# MultiEffect.net
KiCad netlist of a schematic drawn in EAGLE
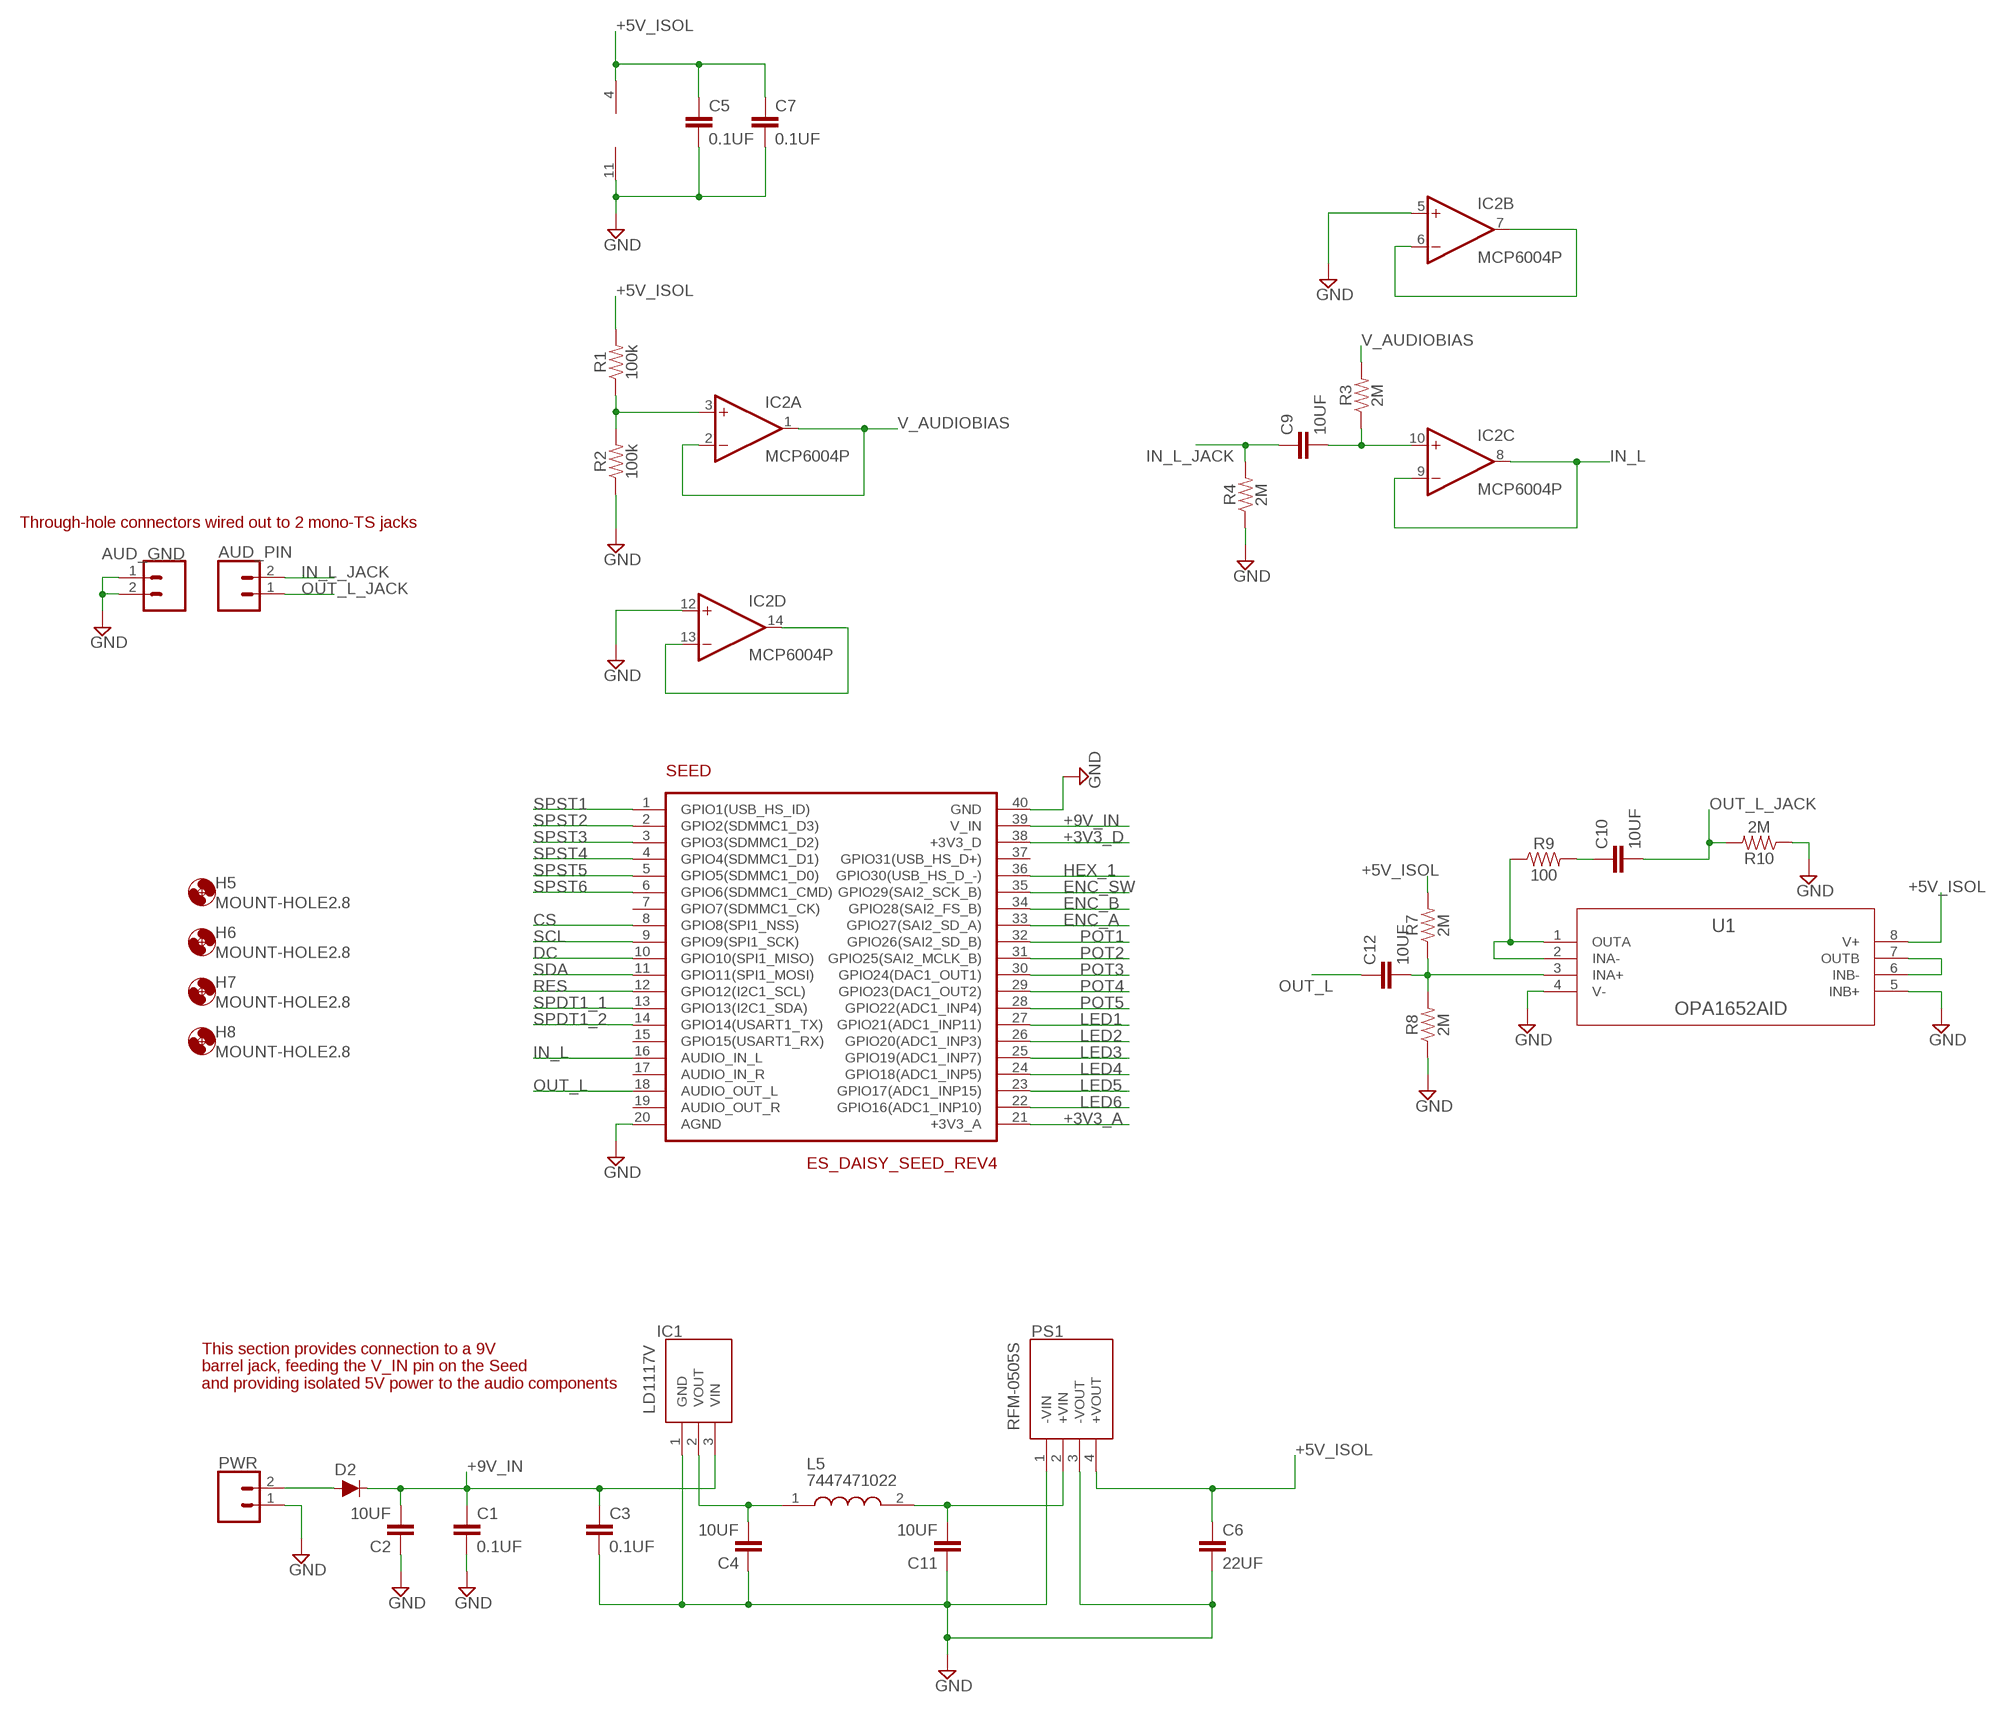
[diagram p0: schematic, sheet 1]
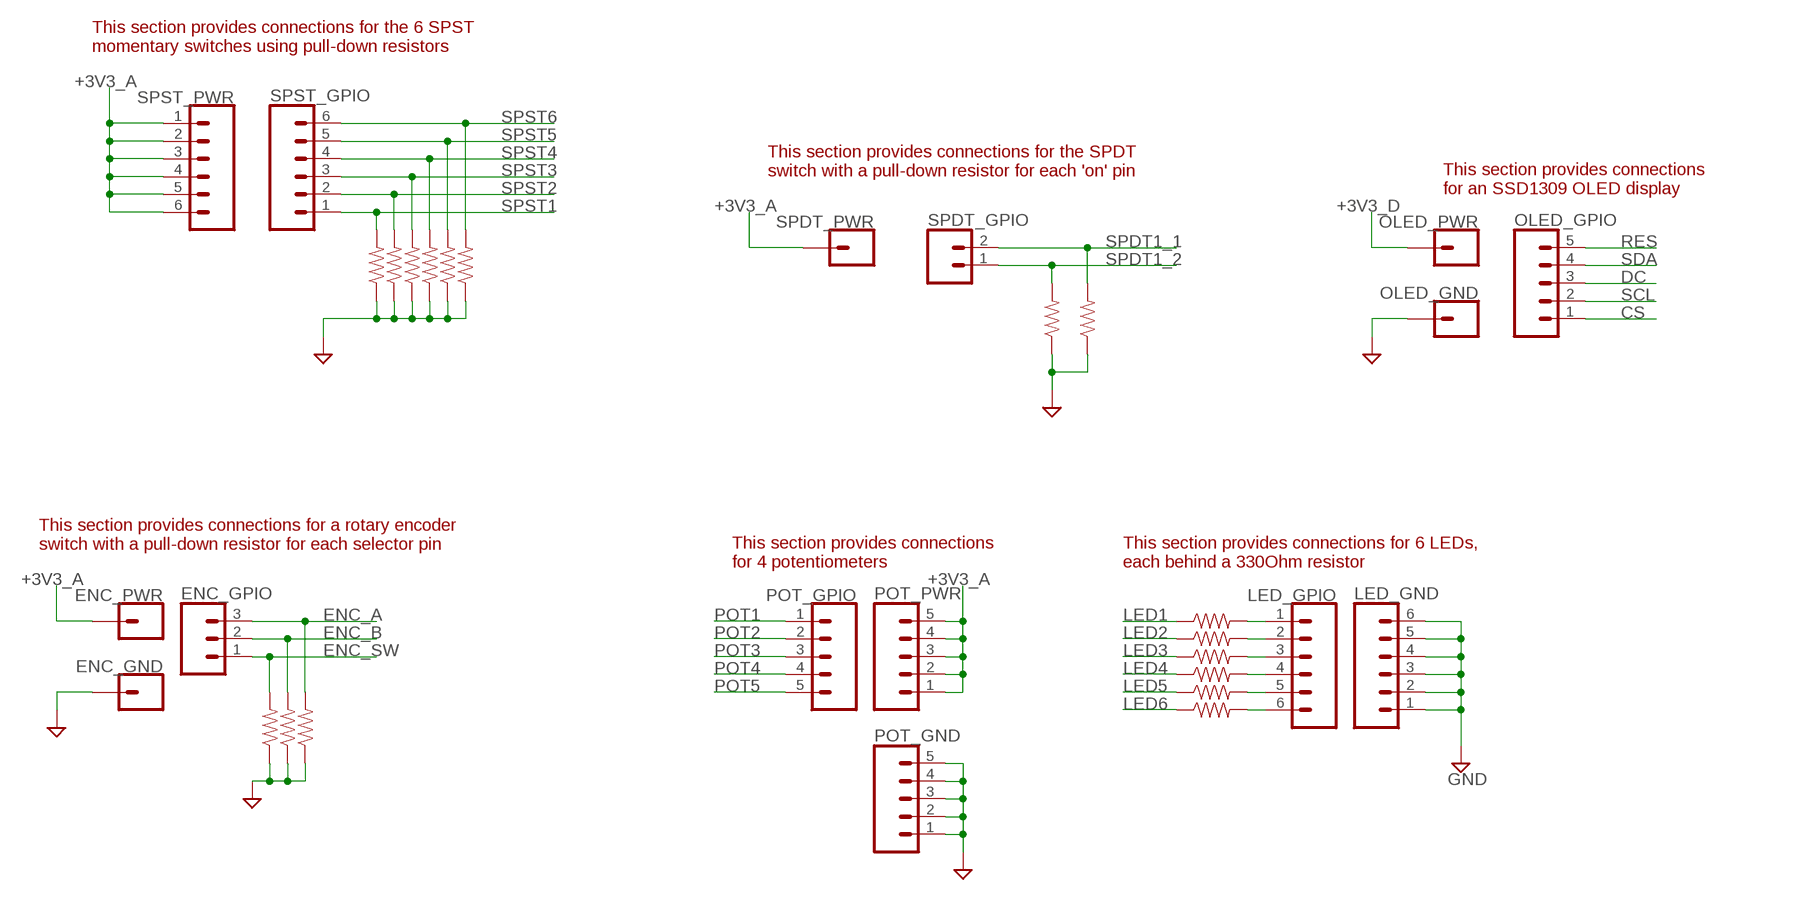
[diagram p1: schematic, sheet 2]

(export (version "E")
  (design (tool "Eeschema 10.0.6"))
  (components
    (comp (ref "AUD_GND")
      (value "CONN_02")
      (footprint "eagle-import:1X02")
      (libsource (lib "eagle-import") (part "CONN_02"))
    )
    (comp (ref "AUD_PIN")
      (value "CONN_02")
      (footprint "eagle-import:1X02")
      (libsource (lib "eagle-import") (part "CONN_02"))
    )
    (comp (ref "C1")
      (value "0.1UF")
      (footprint "eagle-import:CAP-PTH-SMALL-KIT")
      (libsource (lib "eagle-import") (part "0.1UF"))
    )
    (comp (ref "C2")
      (value "10UF")
      (footprint "eagle-import:CAP-PTH-SMALL-KIT")
      (libsource (lib "eagle-import") (part "10UF"))
    )
    (comp (ref "C3")
      (value "0.1UF")
      (footprint "eagle-import:CAP-PTH-SMALL-KIT")
      (libsource (lib "eagle-import") (part "0.1UF"))
    )
    (comp (ref "C4")
      (value "10UF")
      (footprint "eagle-import:CAP-PTH-SMALL-KIT")
      (libsource (lib "eagle-import") (part "10UF"))
    )
    (comp (ref "C5")
      (value "0.1UF")
      (footprint "eagle-import:CAP-PTH-SMALL-KIT")
      (libsource (lib "eagle-import") (part "0.1UF"))
    )
    (comp (ref "C6")
      (value "22UF")
      (footprint "eagle-import:CAP-PTH-SMALL-KIT")
      (libsource (lib "eagle-import") (part "22UF"))
    )
    (comp (ref "C7")
      (value "0.1UF")
      (footprint "eagle-import:CAP-PTH-SMALL-KIT")
      (libsource (lib "eagle-import") (part "0.1UF"))
    )
    (comp (ref "C9")
      (value "10UF")
      (footprint "eagle-import:CAP-PTH-SMALL-KIT")
      (libsource (lib "eagle-import") (part "10UF"))
    )
    (comp (ref "C10")
      (value "10UF")
      (footprint "eagle-import:CAP-PTH-SMALL-KIT")
      (libsource (lib "eagle-import") (part "10UF"))
    )
    (comp (ref "C11")
      (value "10UF")
      (footprint "eagle-import:CAP-PTH-SMALL-KIT")
      (libsource (lib "eagle-import") (part "10UF"))
    )
    (comp (ref "C12")
      (value "10UF")
      (footprint "eagle-import:CAP-PTH-SMALL-KIT")
      (libsource (lib "eagle-import") (part "10UF"))
    )
    (comp (ref "D2")
      (value "200mA/100V/1V")
      (footprint "eagle-import:DIODE-1N4148")
      (libsource (lib "eagle-import") (part "DIODE-1N4148"))
    )
    (comp (ref "H5")
      (value "MOUNT-HOLE2.8")
      (footprint "eagle-import:2,8")
      (libsource (lib "eagle-import") (part "MOUNT-HOLE2.8"))
    )
    (comp (ref "H6")
      (value "MOUNT-HOLE2.8")
      (footprint "eagle-import:2,8")
      (libsource (lib "eagle-import") (part "MOUNT-HOLE2.8"))
    )
    (comp (ref "H7")
      (value "MOUNT-HOLE2.8")
      (footprint "eagle-import:2,8")
      (libsource (lib "eagle-import") (part "MOUNT-HOLE2.8"))
    )
    (comp (ref "H8")
      (value "MOUNT-HOLE2.8")
      (footprint "eagle-import:2,8")
      (libsource (lib "eagle-import") (part "MOUNT-HOLE2.8"))
    )
    (comp (ref "IC1")
      (value "LD1117V")
      (footprint "eagle-import:TO255P460X1020X2008-3P")
      (fields (field (name "MOUSER_PART_NUMBER") "511-LD1117V"))
      (libsource (lib "eagle-import") (part "LD1117V"))
    )
    (comp (ref "IC2")
      (value "MCP6004P")
      (footprint "eagle-import:DIL14")
      (libsource (lib "eagle-import") (part "MCP6004P"))
    )
    (comp (ref "L5")
      (value "7447471022")
      (footprint "eagle-import:WE-TIS_111190")
      (fields (field (name "MOUSER_PART_NUMBER") "710-7447471022"))
      (libsource (lib "eagle-import") (part "7447471022"))
    )
    (comp (ref "PS1")
      (value "RFM-0505S")
      (footprint "eagle-import:RFM0505S")
      (fields (field (name "MOUSER_PART_NUMBER") "919-RFM-0505S"))
      (libsource (lib "eagle-import") (part "RFM-0505S"))
    )
    (comp (ref "PWR")
      (value "CONN_02")
      (footprint "eagle-import:1X02")
      (libsource (lib "eagle-import") (part "CONN_02"))
    )
    (comp (ref "R1")
      (value "100k")
      (footprint "eagle-import:AXIAL-0.3")
      (libsource (lib "eagle-import") (part "100KOHM-HORIZ-1/4W-5%"))
    )
    (comp (ref "R2")
      (value "100k")
      (footprint "eagle-import:AXIAL-0.3")
      (libsource (lib "eagle-import") (part "100KOHM-HORIZ-1/4W-5%"))
    )
    (comp (ref "R3")
      (value "2M")
      (footprint "eagle-import:AXIAL-0.3")
      (libsource (lib "eagle-import") (part "2MOHM-HORIZ-1/4W-5%"))
    )
    (comp (ref "R4")
      (value "2M")
      (footprint "eagle-import:AXIAL-0.3")
      (libsource (lib "eagle-import") (part "2MOHM-HORIZ-1/4W-5%"))
    )
    (comp (ref "R7")
      (value "2M")
      (footprint "eagle-import:AXIAL-0.3")
      (libsource (lib "eagle-import") (part "2MOHM-HORIZ-1/4W-5%"))
    )
    (comp (ref "R8")
      (value "2M")
      (footprint "eagle-import:AXIAL-0.3")
      (libsource (lib "eagle-import") (part "2MOHM-HORIZ-1/4W-5%"))
    )
    (comp (ref "R9")
      (value "100")
      (footprint "eagle-import:AXIAL-0.3")
      (libsource (lib "eagle-import") (part "100OHM-HORIZ-1/4W-1%"))
    )
    (comp (ref "R10")
      (value "2M")
      (footprint "eagle-import:AXIAL-0.3")
      (libsource (lib "eagle-import") (part "2MOHM-HORIZ-1/4W-5%"))
    )
    (comp (ref "SEED")
      (value "ES_DAISY_SEED_REV4")
      (footprint "eagle-import:ES_DAISY_SEED")
      (libsource (lib "eagle-import") (part "ES_DAISY_SEED_REV4"))
    )
    (comp (ref "U1")
      (value "OPA1652AID")
      (footprint "eagle-import:D8")
      (fields
        (field (name "GENERIC_PART_NUMBER") "OPA1652")
        (field (name "MANUFACTURER") "Texas Instruments")
      )
      (libsource (lib "eagle-import") (part "OPA1652AID"))
    )
    (comp (ref "D11")
      (value "10k")
      (footprint "eagle-import:AXIAL-0.3")
      (libsource (lib "eagle-import") (part "10KOHM-HORIZ-1/4W-5%"))
    )
    (comp (ref "D12")
      (value "10k")
      (footprint "eagle-import:AXIAL-0.3")
      (libsource (lib "eagle-import") (part "10KOHM-HORIZ-1/4W-5%"))
    )
    (comp (ref "ENC_GND")
      (value "CONN_01")
      (footprint "eagle-import:1X01")
      (libsource (lib "eagle-import") (part "CONN_01"))
    )
    (comp (ref "ENC_GPIO")
      (value "CONN_03")
      (footprint "eagle-import:1X03")
      (libsource (lib "eagle-import") (part "CONN_03"))
    )
    (comp (ref "ENC_PWR")
      (value "CONN_01")
      (footprint "eagle-import:1X01")
      (libsource (lib "eagle-import") (part "CONN_01"))
    )
    (comp (ref "H2")
      (value "10k")
      (footprint "eagle-import:AXIAL-0.3")
      (libsource (lib "eagle-import") (part "10KOHM-HORIZ-1/4W-5%"))
    )
    (comp (ref "H3")
      (value "10k")
      (footprint "eagle-import:AXIAL-0.3")
      (libsource (lib "eagle-import") (part "10KOHM-HORIZ-1/4W-5%"))
    )
    (comp (ref "H4")
      (value "10k")
      (footprint "eagle-import:AXIAL-0.3")
      (libsource (lib "eagle-import") (part "10KOHM-HORIZ-1/4W-5%"))
    )
    (comp (ref "L1")
      (value "330")
      (footprint "eagle-import:AXIAL-0.3")
      (libsource (lib "eagle-import") (part "330OHM-HORIZ-1/10W-5%"))
    )
    (comp (ref "L2")
      (value "330")
      (footprint "eagle-import:AXIAL-0.3")
      (libsource (lib "eagle-import") (part "330OHM-HORIZ-1/10W-5%"))
    )
    (comp (ref "L3")
      (value "330")
      (footprint "eagle-import:AXIAL-0.3")
      (libsource (lib "eagle-import") (part "330OHM-HORIZ-1/10W-5%"))
    )
    (comp (ref "L4")
      (value "330")
      (footprint "eagle-import:AXIAL-0.3")
      (libsource (lib "eagle-import") (part "330OHM-HORIZ-1/10W-5%"))
    )
    (comp (ref "L6")
      (value "330")
      (footprint "eagle-import:AXIAL-0.3")
      (libsource (lib "eagle-import") (part "330OHM-HORIZ-1/10W-5%"))
    )
    (comp (ref "L7")
      (value "330")
      (footprint "eagle-import:AXIAL-0.3")
      (libsource (lib "eagle-import") (part "330OHM-HORIZ-1/10W-5%"))
    )
    (comp (ref "LED_GND")
      (value "CONN_06SILK_FEMALE_PTH")
      (footprint "eagle-import:1X06")
      (libsource (lib "eagle-import") (part "CONN_06SILK_FEMALE_PTH"))
    )
    (comp (ref "LED_GPIO")
      (value "CONN_06SILK_FEMALE_PTH")
      (footprint "eagle-import:1X06")
      (libsource (lib "eagle-import") (part "CONN_06SILK_FEMALE_PTH"))
    )
    (comp (ref "OLED_GND")
      (value "CONN_01")
      (footprint "eagle-import:1X01")
      (libsource (lib "eagle-import") (part "CONN_01"))
    )
    (comp (ref "OLED_GPIO")
      (value "CONN_05")
      (footprint "eagle-import:1X05")
      (libsource (lib "eagle-import") (part "CONN_05"))
    )
    (comp (ref "OLED_PWR")
      (value "CONN_01")
      (footprint "eagle-import:1X01")
      (libsource (lib "eagle-import") (part "CONN_01"))
    )
    (comp (ref "POT_GND")
      (value "CONN_05")
      (footprint "eagle-import:1X05")
      (libsource (lib "eagle-import") (part "CONN_05"))
    )
    (comp (ref "POT_GPIO")
      (value "CONN_05")
      (footprint "eagle-import:1X05")
      (libsource (lib "eagle-import") (part "CONN_05"))
    )
    (comp (ref "POT_PWR")
      (value "CONN_05")
      (footprint "eagle-import:1X05")
      (libsource (lib "eagle-import") (part "CONN_05"))
    )
    (comp (ref "S1")
      (value "10k")
      (footprint "eagle-import:AXIAL-0.3")
      (libsource (lib "eagle-import") (part "10KOHM-HORIZ-1/4W-5%"))
    )
    (comp (ref "S2")
      (value "10k")
      (footprint "eagle-import:AXIAL-0.3")
      (libsource (lib "eagle-import") (part "10KOHM-HORIZ-1/4W-5%"))
    )
    (comp (ref "S3")
      (value "10k")
      (footprint "eagle-import:AXIAL-0.3")
      (libsource (lib "eagle-import") (part "10KOHM-HORIZ-1/4W-5%"))
    )
    (comp (ref "S4")
      (value "10k")
      (footprint "eagle-import:AXIAL-0.3")
      (libsource (lib "eagle-import") (part "10KOHM-HORIZ-1/4W-5%"))
    )
    (comp (ref "S5")
      (value "10k")
      (footprint "eagle-import:AXIAL-0.3")
      (libsource (lib "eagle-import") (part "10KOHM-HORIZ-1/4W-5%"))
    )
    (comp (ref "S6")
      (value "10k")
      (footprint "eagle-import:AXIAL-0.3")
      (libsource (lib "eagle-import") (part "10KOHM-HORIZ-1/4W-5%"))
    )
    (comp (ref "SPDT_GPIO")
      (value "CONN_02")
      (footprint "eagle-import:1X02")
      (libsource (lib "eagle-import") (part "CONN_02"))
    )
    (comp (ref "SPDT_PWR")
      (value "CONN_01")
      (footprint "eagle-import:1X01")
      (libsource (lib "eagle-import") (part "CONN_01"))
    )
    (comp (ref "SPST_GPIO")
      (value "CONN_06SILK_FEMALE_PTH")
      (footprint "eagle-import:1X06")
      (libsource (lib "eagle-import") (part "CONN_06SILK_FEMALE_PTH"))
    )
    (comp (ref "SPST_PWR")
      (value "CONN_06SILK_FEMALE_PTH")
      (footprint "eagle-import:1X06")
      (libsource (lib "eagle-import") (part "CONN_06SILK_FEMALE_PTH"))
    )
  )
  (nets
    (net (code "1") (name "+3V3_A") (class "Default")
      (node (ref "ENC_PWR") (pin "1") (pinfunction "1_1") (pintype "passive"))
      (node (ref "POT_PWR") (pin "1") (pinfunction "1_1") (pintype "passive"))
      (node (ref "POT_PWR") (pin "2") (pinfunction "2_2") (pintype "passive"))
      (node (ref "POT_PWR") (pin "3") (pinfunction "3_3") (pintype "passive"))
      (node (ref "POT_PWR") (pin "4") (pinfunction "4_4") (pintype "passive"))
      (node (ref "POT_PWR") (pin "5") (pinfunction "5_5") (pintype "passive"))
      (node (ref "SEED") (pin "21") (pinfunction "+3V3_A_21") (pintype "bidirectional"))
      (node (ref "SPDT_PWR") (pin "1") (pinfunction "1_1") (pintype "passive"))
      (node (ref "SPST_PWR") (pin "1") (pinfunction "1_1") (pintype "passive"))
      (node (ref "SPST_PWR") (pin "2") (pinfunction "2_2") (pintype "passive"))
      (node (ref "SPST_PWR") (pin "3") (pinfunction "3_3") (pintype "passive"))
      (node (ref "SPST_PWR") (pin "4") (pinfunction "4_4") (pintype "passive"))
      (node (ref "SPST_PWR") (pin "5") (pinfunction "5_5") (pintype "passive"))
      (node (ref "SPST_PWR") (pin "6") (pinfunction "6_6") (pintype "passive"))
    )
    (net (code "2") (name "+3V3_D") (class "Default")
      (node (ref "OLED_PWR") (pin "1") (pinfunction "1_1") (pintype "passive"))
      (node (ref "SEED") (pin "38") (pinfunction "+3V3_D_38") (pintype "bidirectional"))
    )
    (net (code "3") (name "+5V_ISOL") (class "Default")
      (node (ref "C5") (pin "1") (pinfunction "1_1") (pintype "passive"))
      (node (ref "C6") (pin "1") (pinfunction "1_1") (pintype "passive"))
      (node (ref "C7") (pin "1") (pinfunction "1_1") (pintype "passive"))
      (node (ref "IC2") (pin "4") (pinfunction "V+_4") (pintype "power_in"))
      (node (ref "PS1") (pin "4") (pinfunction "+VOUT_4") (pintype "bidirectional"))
      (node (ref "R1") (pin "P$2") (pinfunction "2_P$2") (pintype "passive"))
      (node (ref "R7") (pin "P$2") (pinfunction "2_P$2") (pintype "passive"))
      (node (ref "U1") (pin "8") (pinfunction "V+_8") (pintype "power_in"))
    )
    (net (code "4") (name "+9V_IN") (class "Default")
      (node (ref "C1") (pin "1") (pinfunction "1_1") (pintype "passive"))
      (node (ref "C2") (pin "2") (pinfunction "2_2") (pintype "passive"))
      (node (ref "C3") (pin "1") (pinfunction "1_1") (pintype "passive"))
      (node (ref "D2") (pin "C") (pinfunction "C_C") (pintype "passive"))
      (node (ref "IC1") (pin "3") (pinfunction "VIN_3") (pintype "bidirectional"))
      (node (ref "SEED") (pin "39") (pinfunction "V_IN_39") (pintype "bidirectional"))
    )
    (net (code "5") (name "CS") (class "Default")
      (node (ref "OLED_GPIO") (pin "1") (pinfunction "1_1") (pintype "passive"))
      (node (ref "SEED") (pin "8") (pinfunction "GPIO8(SPI1_NSS)_8") (pintype "bidirectional"))
    )
    (net (code "6") (name "DC") (class "Default")
      (node (ref "OLED_GPIO") (pin "3") (pinfunction "3_3") (pintype "passive"))
      (node (ref "SEED") (pin "10") (pinfunction "GPIO10(SPI1_MISO)_10") (pintype "bidirectional"))
    )
    (net (code "7") (name "ENC_A") (class "Default")
      (node (ref "ENC_GPIO") (pin "3") (pinfunction "3_3") (pintype "passive"))
      (node (ref "H4") (pin "P$2") (pinfunction "2_P$2") (pintype "passive"))
      (node (ref "SEED") (pin "33") (pinfunction "GPIO27(SAI2_SD_A)_33") (pintype "bidirectional"))
    )
    (net (code "8") (name "ENC_B") (class "Default")
      (node (ref "ENC_GPIO") (pin "2") (pinfunction "2_2") (pintype "passive"))
      (node (ref "H3") (pin "P$2") (pinfunction "2_P$2") (pintype "passive"))
      (node (ref "SEED") (pin "34") (pinfunction "GPIO28(SAI2_FS_B)_34") (pintype "bidirectional"))
    )
    (net (code "9") (name "ENC_SW") (class "Default")
      (node (ref "ENC_GPIO") (pin "1") (pinfunction "1_1") (pintype "passive"))
      (node (ref "H2") (pin "P$2") (pinfunction "2_P$2") (pintype "passive"))
      (node (ref "SEED") (pin "35") (pinfunction "GPIO29(SAI2_SCK_B)_35") (pintype "bidirectional"))
    )
    (net (code "10") (name "GND") (class "Default")
      (node (ref "AUD_GND") (pin "1") (pinfunction "1_1") (pintype "passive"))
      (node (ref "AUD_GND") (pin "2") (pinfunction "2_2") (pintype "passive"))
      (node (ref "C1") (pin "2") (pinfunction "2_2") (pintype "passive"))
      (node (ref "C11") (pin "1") (pinfunction "1_1") (pintype "passive"))
      (node (ref "C2") (pin "1") (pinfunction "1_1") (pintype "passive"))
      (node (ref "C3") (pin "2") (pinfunction "2_2") (pintype "passive"))
      (node (ref "C4") (pin "1") (pinfunction "1_1") (pintype "passive"))
      (node (ref "C5") (pin "2") (pinfunction "2_2") (pintype "passive"))
      (node (ref "C6") (pin "2") (pinfunction "2_2") (pintype "passive"))
      (node (ref "C7") (pin "2") (pinfunction "2_2") (pintype "passive"))
      (node (ref "D11") (pin "P$1") (pinfunction "1_P$1") (pintype "passive"))
      (node (ref "D12") (pin "P$1") (pinfunction "1_P$1") (pintype "passive"))
      (node (ref "ENC_GND") (pin "1") (pinfunction "1_1") (pintype "passive"))
      (node (ref "H2") (pin "P$1") (pinfunction "1_P$1") (pintype "passive"))
      (node (ref "H3") (pin "P$1") (pinfunction "1_P$1") (pintype "passive"))
      (node (ref "H4") (pin "P$1") (pinfunction "1_P$1") (pintype "passive"))
      (node (ref "IC1") (pin "1") (pinfunction "GND_1") (pintype "bidirectional"))
      (node (ref "IC2") (pin "11") (pinfunction "V-_11") (pintype "power_in"))
      (node (ref "IC2") (pin "12") (pinfunction "+IN_12") (pintype "input"))
      (node (ref "IC2") (pin "5") (pinfunction "+IN_5") (pintype "input"))
      (node (ref "LED_GND") (pin "1") (pinfunction "1_1") (pintype "passive"))
      (node (ref "LED_GND") (pin "2") (pinfunction "2_2") (pintype "passive"))
      (node (ref "LED_GND") (pin "3") (pinfunction "3_3") (pintype "passive"))
      (node (ref "LED_GND") (pin "4") (pinfunction "4_4") (pintype "passive"))
      (node (ref "LED_GND") (pin "5") (pinfunction "5_5") (pintype "passive"))
      (node (ref "LED_GND") (pin "6") (pinfunction "6_6") (pintype "passive"))
      (node (ref "OLED_GND") (pin "1") (pinfunction "1_1") (pintype "passive"))
      (node (ref "POT_GND") (pin "1") (pinfunction "1_1") (pintype "passive"))
      (node (ref "POT_GND") (pin "2") (pinfunction "2_2") (pintype "passive"))
      (node (ref "POT_GND") (pin "3") (pinfunction "3_3") (pintype "passive"))
      (node (ref "POT_GND") (pin "4") (pinfunction "4_4") (pintype "passive"))
      (node (ref "POT_GND") (pin "5") (pinfunction "5_5") (pintype "passive"))
      (node (ref "PS1") (pin "1") (pinfunction "-VIN_1") (pintype "bidirectional"))
      (node (ref "PS1") (pin "3") (pinfunction "-VOUT_3") (pintype "bidirectional"))
      (node (ref "PWR") (pin "1") (pinfunction "1_1") (pintype "passive"))
      (node (ref "R10") (pin "P$1") (pinfunction "1_P$1") (pintype "passive"))
      (node (ref "R2") (pin "P$1") (pinfunction "1_P$1") (pintype "passive"))
      (node (ref "R4") (pin "P$1") (pinfunction "1_P$1") (pintype "passive"))
      (node (ref "R8") (pin "P$1") (pinfunction "1_P$1") (pintype "passive"))
      (node (ref "S1") (pin "P$1") (pinfunction "1_P$1") (pintype "passive"))
      (node (ref "S2") (pin "P$1") (pinfunction "1_P$1") (pintype "passive"))
      (node (ref "S3") (pin "P$1") (pinfunction "1_P$1") (pintype "passive"))
      (node (ref "S4") (pin "P$1") (pinfunction "1_P$1") (pintype "passive"))
      (node (ref "S5") (pin "P$1") (pinfunction "1_P$1") (pintype "passive"))
      (node (ref "S6") (pin "P$1") (pinfunction "1_P$1") (pintype "passive"))
      (node (ref "SEED") (pin "20") (pinfunction "AGND_20") (pintype "bidirectional"))
      (node (ref "SEED") (pin "40") (pinfunction "GND_40") (pintype "bidirectional"))
      (node (ref "U1") (pin "4") (pinfunction "V-_4") (pintype "power_in"))
      (node (ref "U1") (pin "5") (pinfunction "INB+_5") (pintype "input"))
    )
    (net (code "11") (name "HEX_1") (class "Default")
      (node (ref "SEED") (pin "36") (pinfunction "GPIO30(USB_HS_D_-)_36") (pintype "bidirectional"))
    )
    (net (code "12") (name "IN_L") (class "Default")
      (node (ref "IC2") (pin "8") (pinfunction "OUT_8") (pintype "output"))
      (node (ref "IC2") (pin "9") (pinfunction "-IN_9") (pintype "input"))
      (node (ref "SEED") (pin "16") (pinfunction "AUDIO_IN_L_16") (pintype "bidirectional"))
    )
    (net (code "13") (name "IN_L_JACK") (class "Default")
      (node (ref "AUD_PIN") (pin "2") (pinfunction "2_2") (pintype "passive"))
      (node (ref "C9") (pin "1") (pinfunction "1_1") (pintype "passive"))
      (node (ref "R4") (pin "P$2") (pinfunction "2_P$2") (pintype "passive"))
    )
    (net (code "14") (name "LED1") (class "Default")
      (node (ref "L1") (pin "P$1") (pinfunction "1_P$1") (pintype "passive"))
      (node (ref "SEED") (pin "27") (pinfunction "GPIO21(ADC1_INP11)_27") (pintype "bidirectional"))
    )
    (net (code "15") (name "LED2") (class "Default")
      (node (ref "L2") (pin "P$1") (pinfunction "1_P$1") (pintype "passive"))
      (node (ref "SEED") (pin "26") (pinfunction "GPIO20(ADC1_INP3)_26") (pintype "bidirectional"))
    )
    (net (code "16") (name "LED3") (class "Default")
      (node (ref "L3") (pin "P$1") (pinfunction "1_P$1") (pintype "passive"))
      (node (ref "SEED") (pin "25") (pinfunction "GPIO19(ADC1_INP7)_25") (pintype "bidirectional"))
    )
    (net (code "17") (name "LED4") (class "Default")
      (node (ref "L4") (pin "P$1") (pinfunction "1_P$1") (pintype "passive"))
      (node (ref "SEED") (pin "24") (pinfunction "GPIO18(ADC1_INP5)_24") (pintype "bidirectional"))
    )
    (net (code "18") (name "LED5") (class "Default")
      (node (ref "L6") (pin "P$1") (pinfunction "1_P$1") (pintype "passive"))
      (node (ref "SEED") (pin "23") (pinfunction "GPIO17(ADC1_INP15)_23") (pintype "bidirectional"))
    )
    (net (code "19") (name "LED6") (class "Default")
      (node (ref "L7") (pin "P$1") (pinfunction "1_P$1") (pintype "passive"))
      (node (ref "SEED") (pin "22") (pinfunction "GPIO16(ADC1_INP10)_22") (pintype "bidirectional"))
    )
    (net (code "20") (name "Net-(D2-PadA)") (class "Default")
      (node (ref "D2") (pin "A") (pinfunction "A_A") (pintype "passive"))
      (node (ref "PWR") (pin "2") (pinfunction "2_2") (pintype "passive"))
    )
    (net (code "21") (name "Net-(IC1-VOUT)") (class "Default")
      (node (ref "C4") (pin "2") (pinfunction "2_2") (pintype "passive"))
      (node (ref "IC1") (pin "2") (pinfunction "VOUT_2") (pintype "bidirectional"))
      (node (ref "L5") (pin "1") (pinfunction "1_1") (pintype "bidirectional"))
    )
    (net (code "22") (name "Net-(IC2A-+IN)") (class "Default")
      (node (ref "IC2") (pin "3") (pinfunction "+IN_3") (pintype "input"))
      (node (ref "R1") (pin "P$1") (pinfunction "1_P$1") (pintype "passive"))
      (node (ref "R2") (pin "P$2") (pinfunction "2_P$2") (pintype "passive"))
    )
    (net (code "23") (name "Net-(IC2B--IN)") (class "Default")
      (node (ref "IC2") (pin "6") (pinfunction "-IN_6") (pintype "input"))
      (node (ref "IC2") (pin "7") (pinfunction "OUT_7") (pintype "output"))
    )
    (net (code "24") (name "Net-(IC2C-+IN)") (class "Default")
      (node (ref "C9") (pin "2") (pinfunction "2_2") (pintype "passive"))
      (node (ref "IC2") (pin "10") (pinfunction "+IN_10") (pintype "input"))
      (node (ref "R3") (pin "P$1") (pinfunction "1_P$1") (pintype "passive"))
    )
    (net (code "25") (name "Net-(IC2D--IN)") (class "Default")
      (node (ref "IC2") (pin "13") (pinfunction "-IN_13") (pintype "input"))
      (node (ref "IC2") (pin "14") (pinfunction "OUT_14") (pintype "output"))
    )
    (net (code "26") (name "Net-(L1-2)") (class "Default")
      (node (ref "L1") (pin "P$2") (pinfunction "2_P$2") (pintype "passive"))
      (node (ref "LED_GPIO") (pin "1") (pinfunction "1_1") (pintype "passive"))
    )
    (net (code "27") (name "Net-(L2-2)") (class "Default")
      (node (ref "L2") (pin "P$2") (pinfunction "2_P$2") (pintype "passive"))
      (node (ref "LED_GPIO") (pin "2") (pinfunction "2_2") (pintype "passive"))
    )
    (net (code "28") (name "Net-(L3-2)") (class "Default")
      (node (ref "L3") (pin "P$2") (pinfunction "2_P$2") (pintype "passive"))
      (node (ref "LED_GPIO") (pin "3") (pinfunction "3_3") (pintype "passive"))
    )
    (net (code "29") (name "Net-(L4-2)") (class "Default")
      (node (ref "L4") (pin "P$2") (pinfunction "2_P$2") (pintype "passive"))
      (node (ref "LED_GPIO") (pin "4") (pinfunction "4_4") (pintype "passive"))
    )
    (net (code "30") (name "Net-(L6-2)") (class "Default")
      (node (ref "L6") (pin "P$2") (pinfunction "2_P$2") (pintype "passive"))
      (node (ref "LED_GPIO") (pin "5") (pinfunction "5_5") (pintype "passive"))
    )
    (net (code "31") (name "Net-(L7-2)") (class "Default")
      (node (ref "L7") (pin "P$2") (pinfunction "2_P$2") (pintype "passive"))
      (node (ref "LED_GPIO") (pin "6") (pinfunction "6_6") (pintype "passive"))
    )
    (net (code "32") (name "Net-(PS1-+VIN)") (class "Default")
      (node (ref "C11") (pin "2") (pinfunction "2_2") (pintype "passive"))
      (node (ref "L5") (pin "2") (pinfunction "2_2") (pintype "bidirectional"))
      (node (ref "PS1") (pin "2") (pinfunction "+VIN_2") (pintype "bidirectional"))
    )
    (net (code "33") (name "Net-(R7-1)") (class "Default")
      (node (ref "C12") (pin "2") (pinfunction "2_2") (pintype "passive"))
      (node (ref "R7") (pin "P$1") (pinfunction "1_P$1") (pintype "passive"))
      (node (ref "R8") (pin "P$2") (pinfunction "2_P$2") (pintype "passive"))
      (node (ref "U1") (pin "3") (pinfunction "INA+_3") (pintype "input"))
    )
    (net (code "34") (name "Net-(R9-1)") (class "Default")
      (node (ref "R9") (pin "P$1") (pinfunction "1_P$1") (pintype "passive"))
      (node (ref "U1") (pin "1") (pinfunction "OUTA_1") (pintype "output"))
      (node (ref "U1") (pin "2") (pinfunction "INA-_2") (pintype "input"))
    )
    (net (code "35") (name "Net-(R9-2)") (class "Default")
      (node (ref "C10") (pin "1") (pinfunction "1_1") (pintype "passive"))
      (node (ref "R9") (pin "P$2") (pinfunction "2_P$2") (pintype "passive"))
    )
    (net (code "36") (name "Net-(U1-INB-)") (class "Default")
      (node (ref "U1") (pin "6") (pinfunction "INB-_6") (pintype "input"))
      (node (ref "U1") (pin "7") (pinfunction "OUTB_7") (pintype "output"))
    )
    (net (code "37") (name "OUT_L") (class "Default")
      (node (ref "C12") (pin "1") (pinfunction "1_1") (pintype "passive"))
      (node (ref "SEED") (pin "18") (pinfunction "AUDIO_OUT_L_18") (pintype "bidirectional"))
    )
    (net (code "38") (name "OUT_L_JACK") (class "Default")
      (node (ref "AUD_PIN") (pin "1") (pinfunction "1_1") (pintype "passive"))
      (node (ref "C10") (pin "2") (pinfunction "2_2") (pintype "passive"))
      (node (ref "R10") (pin "P$2") (pinfunction "2_P$2") (pintype "passive"))
    )
    (net (code "39") (name "POT1") (class "Default")
      (node (ref "POT_GPIO") (pin "1") (pinfunction "1_1") (pintype "passive"))
      (node (ref "SEED") (pin "32") (pinfunction "GPIO26(SAI2_SD_B)_32") (pintype "bidirectional"))
    )
    (net (code "40") (name "POT2") (class "Default")
      (node (ref "POT_GPIO") (pin "2") (pinfunction "2_2") (pintype "passive"))
      (node (ref "SEED") (pin "31") (pinfunction "GPIO25(SAI2_MCLK_B)_31") (pintype "bidirectional"))
    )
    (net (code "41") (name "POT3") (class "Default")
      (node (ref "POT_GPIO") (pin "3") (pinfunction "3_3") (pintype "passive"))
      (node (ref "SEED") (pin "30") (pinfunction "GPIO24(DAC1_OUT1)_30") (pintype "bidirectional"))
    )
    (net (code "42") (name "POT4") (class "Default")
      (node (ref "POT_GPIO") (pin "4") (pinfunction "4_4") (pintype "passive"))
      (node (ref "SEED") (pin "29") (pinfunction "GPIO23(DAC1_OUT2)_29") (pintype "bidirectional"))
    )
    (net (code "43") (name "POT5") (class "Default")
      (node (ref "POT_GPIO") (pin "5") (pinfunction "5_5") (pintype "passive"))
      (node (ref "SEED") (pin "28") (pinfunction "GPIO22(ADC1_INP4)_28") (pintype "bidirectional"))
    )
    (net (code "44") (name "RES") (class "Default")
      (node (ref "OLED_GPIO") (pin "5") (pinfunction "5_5") (pintype "passive"))
      (node (ref "SEED") (pin "12") (pinfunction "GPIO12(I2C1_SCL)_12") (pintype "bidirectional"))
    )
    (net (code "45") (name "SCL") (class "Default")
      (node (ref "OLED_GPIO") (pin "2") (pinfunction "2_2") (pintype "passive"))
      (node (ref "SEED") (pin "9") (pinfunction "GPIO9(SPI1_SCK)_9") (pintype "bidirectional"))
    )
    (net (code "46") (name "SDA") (class "Default")
      (node (ref "OLED_GPIO") (pin "4") (pinfunction "4_4") (pintype "passive"))
      (node (ref "SEED") (pin "11") (pinfunction "GPIO11(SPI1_MOSI)_11") (pintype "bidirectional"))
    )
    (net (code "47") (name "SPDT1_1") (class "Default")
      (node (ref "D11") (pin "P$2") (pinfunction "2_P$2") (pintype "passive"))
      (node (ref "SEED") (pin "13") (pinfunction "GPIO13(I2C1_SDA)_13") (pintype "bidirectional"))
      (node (ref "SPDT_GPIO") (pin "2") (pinfunction "2_2") (pintype "passive"))
    )
    (net (code "48") (name "SPDT1_2") (class "Default")
      (node (ref "D12") (pin "P$2") (pinfunction "2_P$2") (pintype "passive"))
      (node (ref "SEED") (pin "14") (pinfunction "GPIO14(USART1_TX)_14") (pintype "bidirectional"))
      (node (ref "SPDT_GPIO") (pin "1") (pinfunction "1_1") (pintype "passive"))
    )
    (net (code "49") (name "SPST1") (class "Default")
      (node (ref "S1") (pin "P$2") (pinfunction "2_P$2") (pintype "passive"))
      (node (ref "SEED") (pin "1") (pinfunction "GPIO1(USB_HS_ID)_1") (pintype "bidirectional"))
      (node (ref "SPST_GPIO") (pin "1") (pinfunction "1_1") (pintype "passive"))
    )
    (net (code "50") (name "SPST2") (class "Default")
      (node (ref "S2") (pin "P$2") (pinfunction "2_P$2") (pintype "passive"))
      (node (ref "SEED") (pin "2") (pinfunction "GPIO2(SDMMC1_D3)_2") (pintype "bidirectional"))
      (node (ref "SPST_GPIO") (pin "2") (pinfunction "2_2") (pintype "passive"))
    )
    (net (code "51") (name "SPST3") (class "Default")
      (node (ref "S3") (pin "P$2") (pinfunction "2_P$2") (pintype "passive"))
      (node (ref "SEED") (pin "3") (pinfunction "GPIO3(SDMMC1_D2)_3") (pintype "bidirectional"))
      (node (ref "SPST_GPIO") (pin "3") (pinfunction "3_3") (pintype "passive"))
    )
    (net (code "52") (name "SPST4") (class "Default")
      (node (ref "S4") (pin "P$2") (pinfunction "2_P$2") (pintype "passive"))
      (node (ref "SEED") (pin "4") (pinfunction "GPIO4(SDMMC1_D1)_4") (pintype "bidirectional"))
      (node (ref "SPST_GPIO") (pin "4") (pinfunction "4_4") (pintype "passive"))
    )
    (net (code "53") (name "SPST5") (class "Default")
      (node (ref "S5") (pin "P$2") (pinfunction "2_P$2") (pintype "passive"))
      (node (ref "SEED") (pin "5") (pinfunction "GPIO5(SDMMC1_D0)_5") (pintype "bidirectional"))
      (node (ref "SPST_GPIO") (pin "5") (pinfunction "5_5") (pintype "passive"))
    )
    (net (code "54") (name "SPST6") (class "Default")
      (node (ref "S6") (pin "P$2") (pinfunction "2_P$2") (pintype "passive"))
      (node (ref "SEED") (pin "6") (pinfunction "GPIO6(SDMMC1_CMD)_6") (pintype "bidirectional"))
      (node (ref "SPST_GPIO") (pin "6") (pinfunction "6_6") (pintype "passive"))
    )
    (net (code "55") (name "V_AUDIOBIAS") (class "Default")
      (node (ref "IC2") (pin "1") (pinfunction "OUT_1") (pintype "output"))
      (node (ref "IC2") (pin "2") (pinfunction "-IN_2") (pintype "input"))
      (node (ref "R3") (pin "P$2") (pinfunction "2_P$2") (pintype "passive"))
    )
    (net (code "56") (name "unconnected-(SEED-AUDIO_IN_R-Pad17)") (class "Default")
      (node (ref "SEED") (pin "17") (pinfunction "AUDIO_IN_R_17") (pintype "bidirectional"))
    )
    (net (code "57") (name "unconnected-(SEED-AUDIO_OUT_R-Pad19)") (class "Default")
      (node (ref "SEED") (pin "19") (pinfunction "AUDIO_OUT_R_19") (pintype "bidirectional"))
    )
    (net (code "58") (name "unconnected-(SEED-GPIO7(SDMMC1_CK)-Pad7)") (class "Default")
      (node (ref "SEED") (pin "7") (pinfunction "GPIO7(SDMMC1_CK)_7") (pintype "bidirectional"))
    )
    (net (code "59") (name "unconnected-(SEED-GPIO15(USART1_RX)-Pad15)") (class "Default")
      (node (ref "SEED") (pin "15") (pinfunction "GPIO15(USART1_RX)_15") (pintype "bidirectional"))
    )
    (net (code "60") (name "unconnected-(SEED-GPIO31(USB_HS_D+)-Pad37)") (class "Default")
      (node (ref "SEED") (pin "37") (pinfunction "GPIO31(USB_HS_D+)_37") (pintype "bidirectional"))
    )
  )
)
